# Stimulation_Stage.net
KiCad netlist of a schematic drawn in Altium Designer
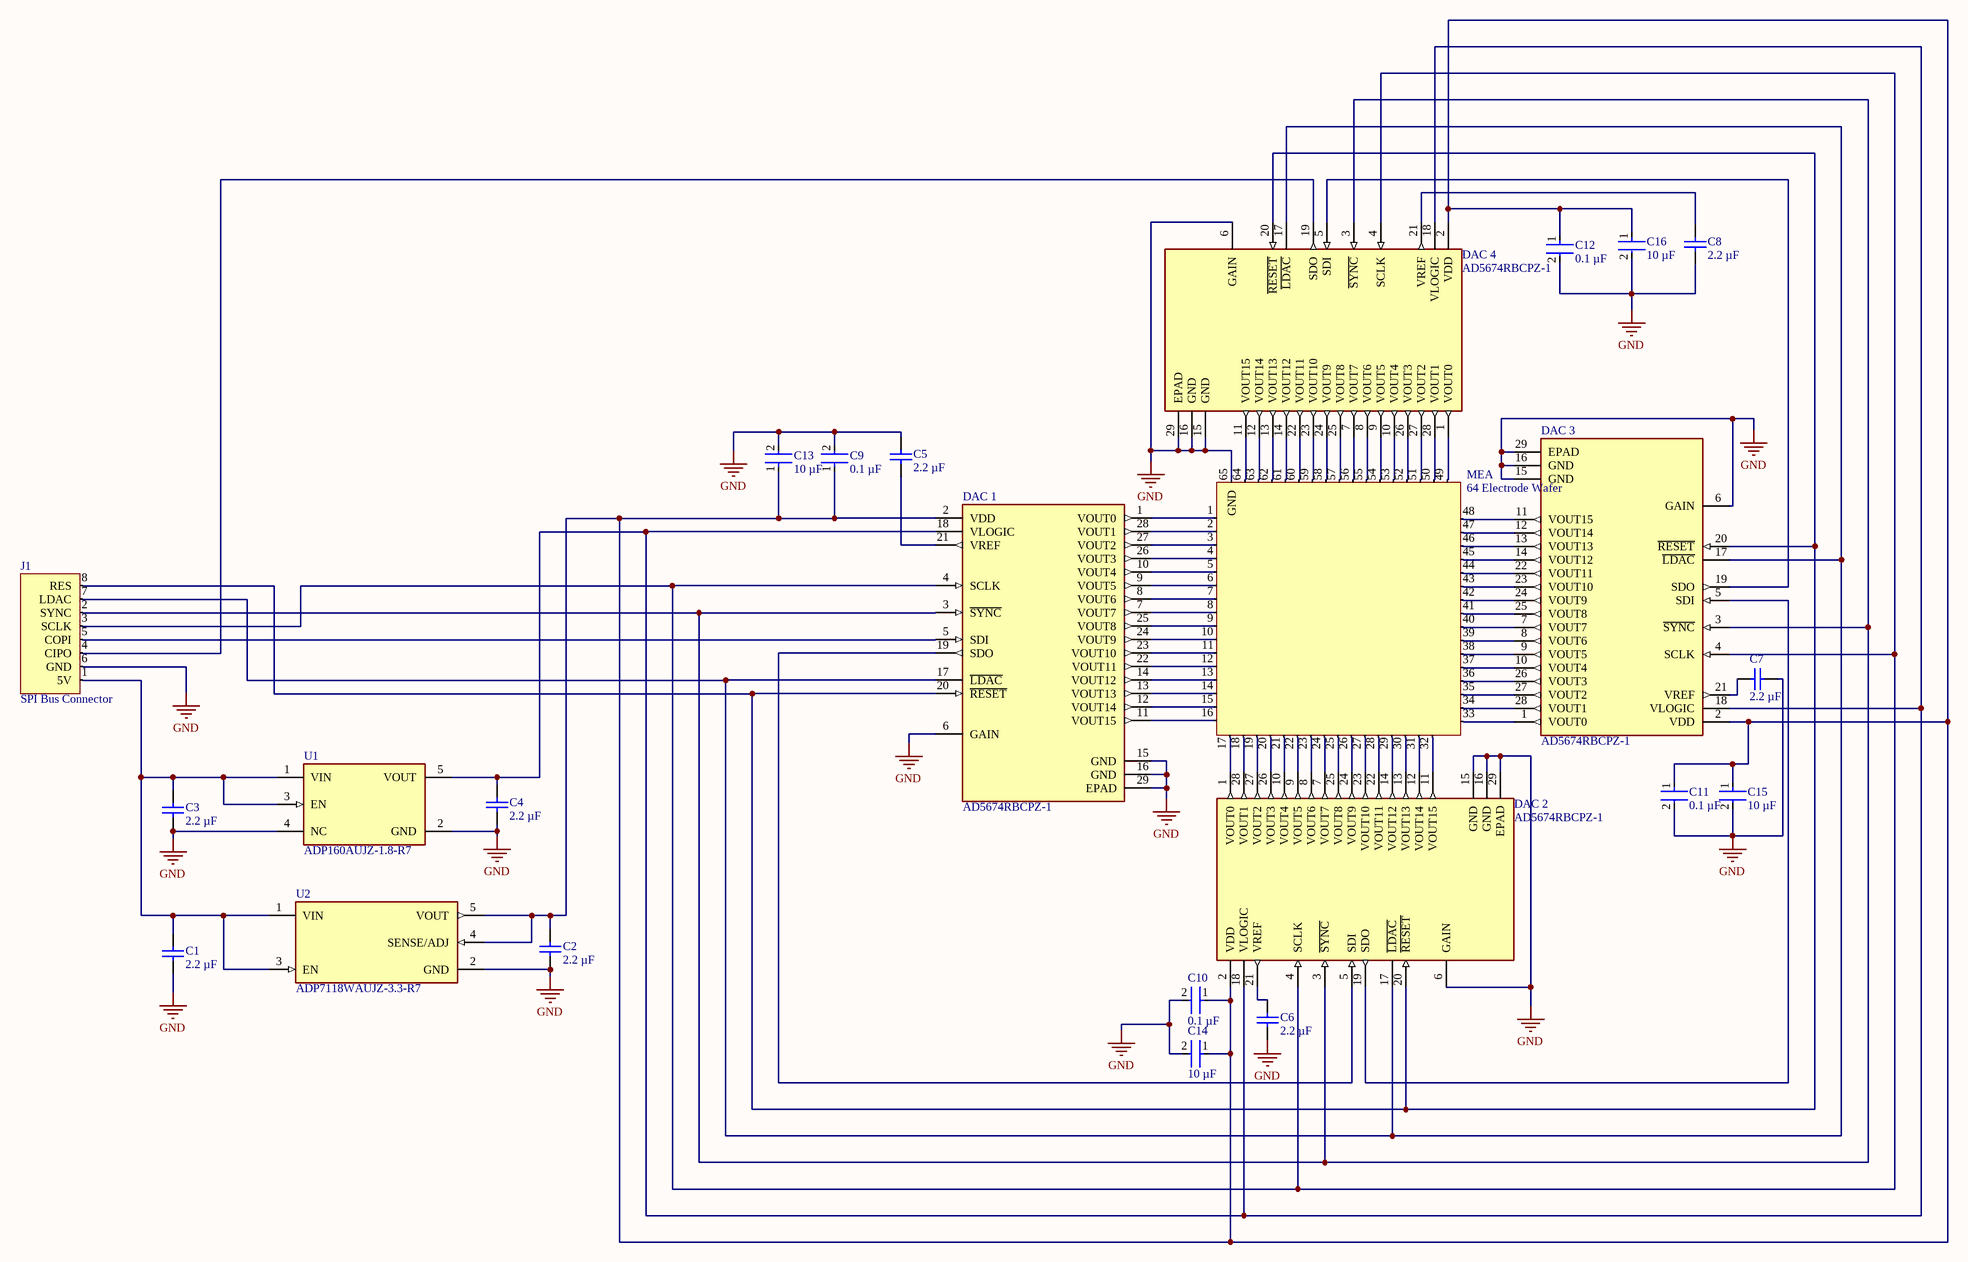
[diagram p0: Stimulation Stage.SchDoc]

(export (version "E")
  (design (tool "Eeschema 10.0.6"))
  (components
    (comp (ref "C1")
      (value "2.2 µF")
      (footprint "CAPC1608X90X30LL10T20")
      (description "Chip Capacitor, 2.2 uF, +/- 10%, 10 V, -55 to 85 degC, 0603 (1608 Metric), RoHS, Tape and Reel")
      (fields (field (name "MANUFACTURER") "Samsung Electro-Mechanics"))
      (libsource (lib "Altium Content Vault") (part "CAP-NP-2"))
    )
    (comp (ref "C2")
      (value "2.2 µF")
      (footprint "CAPC1608X90X30LL10T20")
      (description "Chip Capacitor, 2.2 uF, +/- 10%, 10 V, -55 to 85 degC, 0603 (1608 Metric), RoHS, Tape and Reel")
      (fields (field (name "MANUFACTURER") "Samsung Electro-Mechanics"))
      (libsource (lib "Altium Content Vault") (part "CAP-NP-2"))
    )
    (comp (ref "C3")
      (value "2.2 µF")
      (footprint "CAPC1608X90X30LL10T20")
      (description "Chip Capacitor, 2.2 uF, +/- 10%, 10 V, -55 to 85 degC, 0603 (1608 Metric), RoHS, Tape and Reel")
      (fields (field (name "MANUFACTURER") "Samsung Electro-Mechanics"))
      (libsource (lib "Altium Content Vault") (part "CAP-NP-2"))
    )
    (comp (ref "C4")
      (value "2.2 µF")
      (footprint "CAPC1608X90X30LL10T20")
      (description "Chip Capacitor, 2.2 uF, +/- 10%, 10 V, -55 to 85 degC, 0603 (1608 Metric), RoHS, Tape and Reel")
      (fields (field (name "MANUFACTURER") "Samsung Electro-Mechanics"))
      (libsource (lib "Altium Content Vault") (part "CAP-NP-2"))
    )
    (comp (ref "C5")
      (value "2.2 µF")
      (footprint "CAPC1608X90X30LL10T20")
      (description "Chip Capacitor, 2.2 uF, +/- 10%, 10 V, -55 to 85 degC, 0603 (1608 Metric), RoHS, Tape and Reel")
      (fields (field (name "MANUFACTURER") "Samsung Electro-Mechanics"))
      (libsource (lib "Altium Content Vault") (part "CAP-NP-2"))
    )
    (comp (ref "C6")
      (value "2.2 µF")
      (footprint "CAPC1608X90X30LL10T20")
      (description "Chip Capacitor, 2.2 uF, +/- 10%, 10 V, -55 to 85 degC, 0603 (1608 Metric), RoHS, Tape and Reel")
      (fields (field (name "MANUFACTURER") "Samsung Electro-Mechanics"))
      (libsource (lib "Altium Content Vault") (part "CAP-NP-2"))
    )
    (comp (ref "C7")
      (value "2.2 µF")
      (footprint "CAPC1608X90X30LL10T20")
      (description "Chip Capacitor, 2.2 uF, +/- 10%, 10 V, -55 to 85 degC, 0603 (1608 Metric), RoHS, Tape and Reel")
      (fields (field (name "MANUFACTURER") "Samsung Electro-Mechanics"))
      (libsource (lib "Altium Content Vault") (part "CAP-NP-2"))
    )
    (comp (ref "C8")
      (value "2.2 µF")
      (footprint "CAPC1608X90X30LL10T20")
      (description "Chip Capacitor, 2.2 uF, +/- 10%, 10 V, -55 to 85 degC, 0603 (1608 Metric), RoHS, Tape and Reel")
      (fields (field (name "MANUFACTURER") "Samsung Electro-Mechanics"))
      (libsource (lib "Altium Content Vault") (part "CAP-NP-2"))
    )
    (comp (ref "C9")
      (value "0.1 µF")
      (footprint "FP-CL278-IPC_C")
      (description "Cap Ceramic 100nF 25V X5R ±10% SMD 0402 +85°C Paper T/R")
      (fields (field (name "VOLTAGE") "25V") (field (name "TOLERANCE") "10%"))
      (libsource (lib "Altium Content Vault") (part "b4654b650e69147ec39a6b967a45e02"))
    )
    (comp (ref "C10")
      (value "0.1 µF")
      (footprint "FP-CL278-IPC_C")
      (description "Cap Ceramic 100nF 25V X5R ±10% SMD 0402 +85°C Paper T/R")
      (fields (field (name "VOLTAGE") "25V") (field (name "TOLERANCE") "10%"))
      (libsource (lib "Altium Content Vault") (part "b4654b650e69147ec39a6b967a45e02"))
    )
    (comp (ref "C11")
      (value "0.1 µF")
      (footprint "FP-CL278-IPC_C")
      (description "Cap Ceramic 100nF 25V X5R ±10% SMD 0402 +85°C Paper T/R")
      (fields (field (name "VOLTAGE") "25V") (field (name "TOLERANCE") "10%"))
      (libsource (lib "Altium Content Vault") (part "b4654b650e69147ec39a6b967a45e02"))
    )
    (comp (ref "C12")
      (value "0.1 µF")
      (footprint "FP-CL278-IPC_C")
      (description "Cap Ceramic 100nF 25V X5R ±10% SMD 0402 +85°C Paper T/R")
      (fields (field (name "VOLTAGE") "25V") (field (name "TOLERANCE") "10%"))
      (libsource (lib "Altium Content Vault") (part "b4654b650e69147ec39a6b967a45e02"))
    )
    (comp (ref "C13")
      (value "10 µF")
      (footprint "FP-CL10-IPC_C")
      (description "Cap Ceramic 10uF 6.3V X5R ±20% Pad SMD 0603 +85°C T/R")
      (fields (field (name "VOLTAGE") "6.3V") (field (name "TOLERANCE") "20%"))
      (libsource (lib "Altium Content Vault") (part "b4654b650e69147ec39a6b967a45e02"))
    )
    (comp (ref "C14")
      (value "10 µF")
      (footprint "FP-CL10-IPC_C")
      (description "Cap Ceramic 10uF 6.3V X5R ±20% Pad SMD 0603 +85°C T/R")
      (fields (field (name "VOLTAGE") "6.3V") (field (name "TOLERANCE") "20%"))
      (libsource (lib "Altium Content Vault") (part "b4654b650e69147ec39a6b967a45e02"))
    )
    (comp (ref "C15")
      (value "10 µF")
      (footprint "FP-CL10-IPC_C")
      (description "Cap Ceramic 10uF 6.3V X5R ±20% Pad SMD 0603 +85°C T/R")
      (fields (field (name "VOLTAGE") "6.3V") (field (name "TOLERANCE") "20%"))
      (libsource (lib "Altium Content Vault") (part "b4654b650e69147ec39a6b967a45e02"))
    )
    (comp (ref "C16")
      (value "10 µF")
      (footprint "FP-CL10-IPC_C")
      (description "Cap Ceramic 10uF 6.3V X5R ±20% Pad SMD 0603 +85°C T/R")
      (fields (field (name "VOLTAGE") "6.3V") (field (name "TOLERANCE") "20%"))
      (libsource (lib "Altium Content Vault") (part "b4654b650e69147ec39a6b967a45e02"))
    )
    (comp (ref "DAC 1")
      (value "AD5674RBCPZ-1")
      (footprint "FP-CP-28-9-IPC_C")
      (description "16-CH12-BITNANODAC+WITH2PPM/CREF")
      (libsource (lib "") (part "8444db3836bae7896dad1ad18e8f2a5_2"))
    )
    (comp (ref "DAC 2")
      (value "AD5674RBCPZ-1")
      (footprint "FP-CP-28-9-IPC_C")
      (description "16-CH12-BITNANODAC+WITH2PPM/CREF")
      (libsource (lib "") (part "8444db3836bae7896dad1ad18e8f2a5_1"))
    )
    (comp (ref "DAC 3")
      (value "AD5674RBCPZ-1")
      (footprint "FP-CP-28-9-IPC_C")
      (description "16-CH12-BITNANODAC+WITH2PPM/CREF")
      (libsource (lib "Altium Content Vault") (part "8444db3836bae7896dad1ad18e8f2a5"))
    )
    (comp (ref "DAC 4")
      (value "AD5674RBCPZ-1")
      (footprint "FP-CP-28-9-IPC_C")
      (description "16-CH12-BITNANODAC+WITH2PPM/CREF")
      (libsource (lib "") (part "8444db3836bae7896dad1ad18e8f2a5_3"))
    )
    (comp (ref "J1")
      (value "SPI Bus Connector")
      (footprint "SPI Bus Connector")
      (description "8 pin connector for SPI interface and power from m")
      (libsource (lib "Celestial Library Database") (part "SPI Bus Connector"))
    )
    (comp (ref "MEA")
      (value "64 Electrode Wafer")
      (footprint "64 Electrode Wafer Footprint")
      (description "64 channel transparent Microelectrode Array")
      (libsource (lib "Celestial Library Database") (part "64 Electrode Wafer"))
    )
    (comp (ref "U1")
      (value "ADP160AUJZ-1.8-R7")
      (footprint "FP-UJ-5-IPC_C")
      (description "IC REG LINEAR 1.8V 150MA TSOT5")
      (libsource (lib "Altium Content Vault") (part "49efecb8457b62bbb278fcbf558b656"))
    )
    (comp (ref "U2")
      (value "ADP7118WAUJZ-3.3-R7")
      (footprint "FP-UJ-5-IPC_C")
      (description "IC REG LINEAR 3.3V 200MA TSOT5")
      (libsource (lib "Altium Content Vault") (part "4a7971eea0f250dff842508c33254cb"))
    )
  )
  (nets
    (net (code "1") (name "GND") (class "Default")
      (node (ref "C1") (pin "1") (pinfunction "1_1") (pintype "passive"))
      (node (ref "C10") (pin "2") (pinfunction "2_2") (pintype "passive"))
      (node (ref "C11") (pin "2") (pinfunction "2_2") (pintype "passive"))
      (node (ref "C12") (pin "2") (pinfunction "2_2") (pintype "passive"))
      (node (ref "C13") (pin "2") (pinfunction "2_2") (pintype "passive"))
      (node (ref "C14") (pin "2") (pinfunction "2_2") (pintype "passive"))
      (node (ref "C15") (pin "2") (pinfunction "2_2") (pintype "passive"))
      (node (ref "C16") (pin "2") (pinfunction "2_2") (pintype "passive"))
      (node (ref "C2") (pin "1") (pinfunction "1_1") (pintype "passive"))
      (node (ref "C3") (pin "1") (pinfunction "1_1") (pintype "passive"))
      (node (ref "C4") (pin "1") (pinfunction "1_1") (pintype "passive"))
      (node (ref "C5") (pin "2") (pinfunction "2_2") (pintype "passive"))
      (node (ref "C6") (pin "1") (pinfunction "1_1") (pintype "passive"))
      (node (ref "C7") (pin "1") (pinfunction "1_1") (pintype "passive"))
      (node (ref "C8") (pin "1") (pinfunction "1_1") (pintype "passive"))
      (node (ref "C9") (pin "2") (pinfunction "2_2") (pintype "passive"))
      (node (ref "DAC 1") (pin "15") (pinfunction "GND_15") (pintype "power_in"))
      (node (ref "DAC 1") (pin "16") (pinfunction "GND_16") (pintype "power_in"))
      (node (ref "DAC 1") (pin "29") (pinfunction "EPAD_29") (pintype "power_in"))
      (node (ref "DAC 1") (pin "6") (pinfunction "GAIN_6") (pintype "passive"))
      (node (ref "DAC 2") (pin "15") (pinfunction "GND_15") (pintype "power_in"))
      (node (ref "DAC 2") (pin "16") (pinfunction "GND_16") (pintype "power_in"))
      (node (ref "DAC 2") (pin "29") (pinfunction "EPAD_29") (pintype "power_in"))
      (node (ref "DAC 2") (pin "6") (pinfunction "GAIN_6") (pintype "passive"))
      (node (ref "DAC 3") (pin "15") (pinfunction "GND_15") (pintype "power_in"))
      (node (ref "DAC 3") (pin "16") (pinfunction "GND_16") (pintype "power_in"))
      (node (ref "DAC 3") (pin "29") (pinfunction "EPAD_29") (pintype "power_in"))
      (node (ref "DAC 3") (pin "6") (pinfunction "GAIN_6") (pintype "passive"))
      (node (ref "DAC 4") (pin "15") (pinfunction "GND_15") (pintype "power_in"))
      (node (ref "DAC 4") (pin "16") (pinfunction "GND_16") (pintype "power_in"))
      (node (ref "DAC 4") (pin "29") (pinfunction "EPAD_29") (pintype "power_in"))
      (node (ref "DAC 4") (pin "6") (pinfunction "GAIN_6") (pintype "passive"))
      (node (ref "J1") (pin "6") (pinfunction "GND_6") (pintype "power_in"))
      (node (ref "MEA") (pin "65") (pinfunction "GND_65") (pintype "input"))
      (node (ref "U1") (pin "2") (pinfunction "GND_2") (pintype "power_in"))
      (node (ref "U1") (pin "4") (pinfunction "NC_4") (pintype "passive"))
      (node (ref "U2") (pin "2") (pinfunction "GND_2") (pintype "power_in"))
    )
    (net (code "2") (name "Net-(DAC 1-SCLK)") (class "Default")
      (node (ref "DAC 1") (pin "4") (pinfunction "SCLK_4") (pintype "input"))
      (node (ref "DAC 2") (pin "4") (pinfunction "SCLK_4") (pintype "input"))
      (node (ref "DAC 3") (pin "4") (pinfunction "SCLK_4") (pintype "input"))
      (node (ref "DAC 4") (pin "4") (pinfunction "SCLK_4") (pintype "input"))
      (node (ref "J1") (pin "3") (pinfunction "SCLK_3") (pintype "output"))
    )
    (net (code "3") (name "Net-(DAC 1-SDI)") (class "Default")
      (node (ref "DAC 1") (pin "5") (pinfunction "SDI_5") (pintype "input"))
      (node (ref "J1") (pin "5") (pinfunction "COPI_5") (pintype "output"))
    )
    (net (code "4") (name "Net-(DAC 1-SDO)") (class "Default")
      (node (ref "DAC 1") (pin "19") (pinfunction "SDO_19") (pintype "output"))
      (node (ref "DAC 2") (pin "5") (pinfunction "SDI_5") (pintype "input"))
    )
    (net (code "5") (name "Net-(DAC 1-VDD)") (class "Default")
      (node (ref "C10") (pin "1") (pinfunction "1_1") (pintype "passive"))
      (node (ref "C11") (pin "1") (pinfunction "1_1") (pintype "passive"))
      (node (ref "C12") (pin "1") (pinfunction "1_1") (pintype "passive"))
      (node (ref "C13") (pin "1") (pinfunction "1_1") (pintype "passive"))
      (node (ref "C14") (pin "1") (pinfunction "1_1") (pintype "passive"))
      (node (ref "C15") (pin "1") (pinfunction "1_1") (pintype "passive"))
      (node (ref "C16") (pin "1") (pinfunction "1_1") (pintype "passive"))
      (node (ref "C2") (pin "2") (pinfunction "2_2") (pintype "passive"))
      (node (ref "C9") (pin "1") (pinfunction "1_1") (pintype "passive"))
      (node (ref "DAC 1") (pin "2") (pinfunction "VDD_2") (pintype "power_in"))
      (node (ref "DAC 2") (pin "2") (pinfunction "VDD_2") (pintype "power_in"))
      (node (ref "DAC 3") (pin "2") (pinfunction "VDD_2") (pintype "power_in"))
      (node (ref "DAC 4") (pin "2") (pinfunction "VDD_2") (pintype "power_in"))
      (node (ref "U2") (pin "4") (pinfunction "SENSE/ADJ_4") (pintype "input"))
      (node (ref "U2") (pin "5") (pinfunction "VOUT_5") (pintype "output"))
    )
    (net (code "6") (name "Net-(DAC 1-VLOGIC)") (class "Default")
      (node (ref "C4") (pin "2") (pinfunction "2_2") (pintype "passive"))
      (node (ref "DAC 1") (pin "18") (pinfunction "VLOGIC_18") (pintype "power_in"))
      (node (ref "DAC 2") (pin "18") (pinfunction "VLOGIC_18") (pintype "power_in"))
      (node (ref "DAC 3") (pin "18") (pinfunction "VLOGIC_18") (pintype "power_in"))
      (node (ref "DAC 4") (pin "18") (pinfunction "VLOGIC_18") (pintype "power_in"))
      (node (ref "U1") (pin "5") (pinfunction "VOUT_5") (pintype "power_in"))
    )
    (net (code "7") (name "Net-(DAC 1-VOUT0)") (class "Default")
      (node (ref "DAC 1") (pin "1") (pinfunction "VOUT0_1") (pintype "output"))
      (node (ref "MEA") (pin "1") (pintype "input"))
    )
    (net (code "8") (name "Net-(DAC 1-VOUT1)") (class "Default")
      (node (ref "DAC 1") (pin "28") (pinfunction "VOUT1_28") (pintype "output"))
      (node (ref "MEA") (pin "2") (pintype "input"))
    )
    (net (code "9") (name "Net-(DAC 1-VOUT2)") (class "Default")
      (node (ref "DAC 1") (pin "27") (pinfunction "VOUT2_27") (pintype "output"))
      (node (ref "MEA") (pin "3") (pintype "input"))
    )
    (net (code "10") (name "Net-(DAC 1-VOUT3)") (class "Default")
      (node (ref "DAC 1") (pin "26") (pinfunction "VOUT3_26") (pintype "output"))
      (node (ref "MEA") (pin "4") (pintype "input"))
    )
    (net (code "11") (name "Net-(DAC 1-VOUT4)") (class "Default")
      (node (ref "DAC 1") (pin "10") (pinfunction "VOUT4_10") (pintype "output"))
      (node (ref "MEA") (pin "5") (pintype "input"))
    )
    (net (code "12") (name "Net-(DAC 1-VOUT5)") (class "Default")
      (node (ref "DAC 1") (pin "9") (pinfunction "VOUT5_9") (pintype "output"))
      (node (ref "MEA") (pin "6") (pintype "input"))
    )
    (net (code "13") (name "Net-(DAC 1-VOUT6)") (class "Default")
      (node (ref "DAC 1") (pin "8") (pinfunction "VOUT6_8") (pintype "output"))
      (node (ref "MEA") (pin "7") (pintype "input"))
    )
    (net (code "14") (name "Net-(DAC 1-VOUT7)") (class "Default")
      (node (ref "DAC 1") (pin "7") (pinfunction "VOUT7_7") (pintype "output"))
      (node (ref "MEA") (pin "8") (pintype "input"))
    )
    (net (code "15") (name "Net-(DAC 1-VOUT8)") (class "Default")
      (node (ref "DAC 1") (pin "25") (pinfunction "VOUT8_25") (pintype "output"))
      (node (ref "MEA") (pin "9") (pintype "input"))
    )
    (net (code "16") (name "Net-(DAC 1-VOUT9)") (class "Default")
      (node (ref "DAC 1") (pin "24") (pinfunction "VOUT9_24") (pintype "output"))
      (node (ref "MEA") (pin "10") (pintype "input"))
    )
    (net (code "17") (name "Net-(DAC 1-VOUT10)") (class "Default")
      (node (ref "DAC 1") (pin "23") (pinfunction "VOUT10_23") (pintype "output"))
      (node (ref "MEA") (pin "11") (pintype "input"))
    )
    (net (code "18") (name "Net-(DAC 1-VOUT11)") (class "Default")
      (node (ref "DAC 1") (pin "22") (pinfunction "VOUT11_22") (pintype "output"))
      (node (ref "MEA") (pin "12") (pintype "input"))
    )
    (net (code "19") (name "Net-(DAC 1-VOUT12)") (class "Default")
      (node (ref "DAC 1") (pin "14") (pinfunction "VOUT12_14") (pintype "output"))
      (node (ref "MEA") (pin "13") (pintype "input"))
    )
    (net (code "20") (name "Net-(DAC 1-VOUT13)") (class "Default")
      (node (ref "DAC 1") (pin "13") (pinfunction "VOUT13_13") (pintype "output"))
      (node (ref "MEA") (pin "14") (pintype "input"))
    )
    (net (code "21") (name "Net-(DAC 1-VOUT14)") (class "Default")
      (node (ref "DAC 1") (pin "12") (pinfunction "VOUT14_12") (pintype "output"))
      (node (ref "MEA") (pin "15") (pintype "input"))
    )
    (net (code "22") (name "Net-(DAC 1-VOUT15)") (class "Default")
      (node (ref "DAC 1") (pin "11") (pinfunction "VOUT15_11") (pintype "output"))
      (node (ref "MEA") (pin "16") (pintype "input"))
    )
    (net (code "23") (name "Net-(DAC 1-VREF)") (class "Default")
      (node (ref "C5") (pin "1") (pinfunction "1_1") (pintype "passive"))
      (node (ref "DAC 1") (pin "21") (pinfunction "VREF_21") (pintype "output"))
    )
    (net (code "24") (name "Net-(DAC 1-~{LDAC})") (class "Default")
      (node (ref "DAC 1") (pin "17") (pinfunction "~{LDAC}_17") (pintype "passive"))
      (node (ref "DAC 2") (pin "17") (pinfunction "~{LDAC}_17") (pintype "passive"))
      (node (ref "DAC 3") (pin "17") (pinfunction "~{LDAC}_17") (pintype "passive"))
      (node (ref "DAC 4") (pin "17") (pinfunction "~{LDAC}_17") (pintype "passive"))
      (node (ref "J1") (pin "7") (pinfunction "LDAC_7") (pintype "output"))
    )
    (net (code "25") (name "Net-(DAC 1-~{RESET})") (class "Default")
      (node (ref "DAC 1") (pin "20") (pinfunction "~{RESET}_20") (pintype "input"))
      (node (ref "DAC 2") (pin "20") (pinfunction "~{RESET}_20") (pintype "input"))
      (node (ref "DAC 3") (pin "20") (pinfunction "~{RESET}_20") (pintype "input"))
      (node (ref "DAC 4") (pin "20") (pinfunction "~{RESET}_20") (pintype "input"))
      (node (ref "J1") (pin "8") (pinfunction "RES_8") (pintype "output"))
    )
    (net (code "26") (name "Net-(DAC 1-~{SYNC})") (class "Default")
      (node (ref "DAC 1") (pin "3") (pinfunction "~{SYNC}_3") (pintype "input"))
      (node (ref "DAC 2") (pin "3") (pinfunction "~{SYNC}_3") (pintype "input"))
      (node (ref "DAC 3") (pin "3") (pinfunction "~{SYNC}_3") (pintype "input"))
      (node (ref "DAC 4") (pin "3") (pinfunction "~{SYNC}_3") (pintype "input"))
      (node (ref "J1") (pin "2") (pinfunction "SYNC_2") (pintype "output"))
    )
    (net (code "27") (name "Net-(DAC 2-SDO)") (class "Default")
      (node (ref "DAC 2") (pin "19") (pinfunction "SDO_19") (pintype "output"))
      (node (ref "DAC 3") (pin "5") (pinfunction "SDI_5") (pintype "input"))
    )
    (net (code "28") (name "Net-(DAC 2-VOUT0)") (class "Default")
      (node (ref "DAC 2") (pin "1") (pinfunction "VOUT0_1") (pintype "output"))
      (node (ref "MEA") (pin "17") (pintype "input"))
    )
    (net (code "29") (name "Net-(DAC 2-VOUT1)") (class "Default")
      (node (ref "DAC 2") (pin "28") (pinfunction "VOUT1_28") (pintype "output"))
      (node (ref "MEA") (pin "18") (pintype "input"))
    )
    (net (code "30") (name "Net-(DAC 2-VOUT2)") (class "Default")
      (node (ref "DAC 2") (pin "27") (pinfunction "VOUT2_27") (pintype "output"))
      (node (ref "MEA") (pin "19") (pintype "input"))
    )
    (net (code "31") (name "Net-(DAC 2-VOUT3)") (class "Default")
      (node (ref "DAC 2") (pin "26") (pinfunction "VOUT3_26") (pintype "output"))
      (node (ref "MEA") (pin "20") (pintype "input"))
    )
    (net (code "32") (name "Net-(DAC 2-VOUT4)") (class "Default")
      (node (ref "DAC 2") (pin "10") (pinfunction "VOUT4_10") (pintype "output"))
      (node (ref "MEA") (pin "21") (pintype "input"))
    )
    (net (code "33") (name "Net-(DAC 2-VOUT5)") (class "Default")
      (node (ref "DAC 2") (pin "9") (pinfunction "VOUT5_9") (pintype "output"))
      (node (ref "MEA") (pin "22") (pintype "input"))
    )
    (net (code "34") (name "Net-(DAC 2-VOUT6)") (class "Default")
      (node (ref "DAC 2") (pin "8") (pinfunction "VOUT6_8") (pintype "output"))
      (node (ref "MEA") (pin "23") (pintype "input"))
    )
    (net (code "35") (name "Net-(DAC 2-VOUT7)") (class "Default")
      (node (ref "DAC 2") (pin "7") (pinfunction "VOUT7_7") (pintype "output"))
      (node (ref "MEA") (pin "24") (pintype "input"))
    )
    (net (code "36") (name "Net-(DAC 2-VOUT8)") (class "Default")
      (node (ref "DAC 2") (pin "25") (pinfunction "VOUT8_25") (pintype "output"))
      (node (ref "MEA") (pin "25") (pintype "input"))
    )
    (net (code "37") (name "Net-(DAC 2-VOUT9)") (class "Default")
      (node (ref "DAC 2") (pin "24") (pinfunction "VOUT9_24") (pintype "output"))
      (node (ref "MEA") (pin "26") (pintype "input"))
    )
    (net (code "38") (name "Net-(DAC 2-VOUT10)") (class "Default")
      (node (ref "DAC 2") (pin "23") (pinfunction "VOUT10_23") (pintype "output"))
      (node (ref "MEA") (pin "27") (pintype "input"))
    )
    (net (code "39") (name "Net-(DAC 2-VOUT11)") (class "Default")
      (node (ref "DAC 2") (pin "22") (pinfunction "VOUT11_22") (pintype "output"))
      (node (ref "MEA") (pin "28") (pintype "input"))
    )
    (net (code "40") (name "Net-(DAC 2-VOUT12)") (class "Default")
      (node (ref "DAC 2") (pin "14") (pinfunction "VOUT12_14") (pintype "output"))
      (node (ref "MEA") (pin "29") (pintype "input"))
    )
    (net (code "41") (name "Net-(DAC 2-VOUT13)") (class "Default")
      (node (ref "DAC 2") (pin "13") (pinfunction "VOUT13_13") (pintype "output"))
      (node (ref "MEA") (pin "30") (pintype "input"))
    )
    (net (code "42") (name "Net-(DAC 2-VOUT14)") (class "Default")
      (node (ref "DAC 2") (pin "12") (pinfunction "VOUT14_12") (pintype "output"))
      (node (ref "MEA") (pin "31") (pintype "input"))
    )
    (net (code "43") (name "Net-(DAC 2-VOUT15)") (class "Default")
      (node (ref "DAC 2") (pin "11") (pinfunction "VOUT15_11") (pintype "output"))
      (node (ref "MEA") (pin "32") (pintype "input"))
    )
    (net (code "44") (name "Net-(DAC 2-VREF)") (class "Default")
      (node (ref "C6") (pin "2") (pinfunction "2_2") (pintype "passive"))
      (node (ref "DAC 2") (pin "21") (pinfunction "VREF_21") (pintype "output"))
    )
    (net (code "45") (name "Net-(DAC 3-SDO)") (class "Default")
      (node (ref "DAC 3") (pin "19") (pinfunction "SDO_19") (pintype "output"))
      (node (ref "DAC 4") (pin "5") (pinfunction "SDI_5") (pintype "input"))
    )
    (net (code "46") (name "Net-(DAC 3-VOUT0)") (class "Default")
      (node (ref "DAC 3") (pin "1") (pinfunction "VOUT0_1") (pintype "output"))
      (node (ref "MEA") (pin "33") (pintype "input"))
    )
    (net (code "47") (name "Net-(DAC 3-VOUT1)") (class "Default")
      (node (ref "DAC 3") (pin "28") (pinfunction "VOUT1_28") (pintype "output"))
      (node (ref "MEA") (pin "34") (pintype "input"))
    )
    (net (code "48") (name "Net-(DAC 3-VOUT2)") (class "Default")
      (node (ref "DAC 3") (pin "27") (pinfunction "VOUT2_27") (pintype "output"))
      (node (ref "MEA") (pin "35") (pintype "input"))
    )
    (net (code "49") (name "Net-(DAC 3-VOUT3)") (class "Default")
      (node (ref "DAC 3") (pin "26") (pinfunction "VOUT3_26") (pintype "output"))
      (node (ref "MEA") (pin "36") (pintype "input"))
    )
    (net (code "50") (name "Net-(DAC 3-VOUT4)") (class "Default")
      (node (ref "DAC 3") (pin "10") (pinfunction "VOUT4_10") (pintype "output"))
      (node (ref "MEA") (pin "37") (pintype "input"))
    )
    (net (code "51") (name "Net-(DAC 3-VOUT5)") (class "Default")
      (node (ref "DAC 3") (pin "9") (pinfunction "VOUT5_9") (pintype "output"))
      (node (ref "MEA") (pin "38") (pintype "input"))
    )
    (net (code "52") (name "Net-(DAC 3-VOUT6)") (class "Default")
      (node (ref "DAC 3") (pin "8") (pinfunction "VOUT6_8") (pintype "output"))
      (node (ref "MEA") (pin "39") (pintype "input"))
    )
    (net (code "53") (name "Net-(DAC 3-VOUT7)") (class "Default")
      (node (ref "DAC 3") (pin "7") (pinfunction "VOUT7_7") (pintype "output"))
      (node (ref "MEA") (pin "40") (pintype "input"))
    )
    (net (code "54") (name "Net-(DAC 3-VOUT8)") (class "Default")
      (node (ref "DAC 3") (pin "25") (pinfunction "VOUT8_25") (pintype "output"))
      (node (ref "MEA") (pin "41") (pintype "input"))
    )
    (net (code "55") (name "Net-(DAC 3-VOUT9)") (class "Default")
      (node (ref "DAC 3") (pin "24") (pinfunction "VOUT9_24") (pintype "output"))
      (node (ref "MEA") (pin "42") (pintype "input"))
    )
    (net (code "56") (name "Net-(DAC 3-VOUT10)") (class "Default")
      (node (ref "DAC 3") (pin "23") (pinfunction "VOUT10_23") (pintype "output"))
      (node (ref "MEA") (pin "43") (pintype "input"))
    )
    (net (code "57") (name "Net-(DAC 3-VOUT11)") (class "Default")
      (node (ref "DAC 3") (pin "22") (pinfunction "VOUT11_22") (pintype "output"))
      (node (ref "MEA") (pin "44") (pintype "input"))
    )
    (net (code "58") (name "Net-(DAC 3-VOUT12)") (class "Default")
      (node (ref "DAC 3") (pin "14") (pinfunction "VOUT12_14") (pintype "output"))
      (node (ref "MEA") (pin "45") (pintype "input"))
    )
    (net (code "59") (name "Net-(DAC 3-VOUT13)") (class "Default")
      (node (ref "DAC 3") (pin "13") (pinfunction "VOUT13_13") (pintype "output"))
      (node (ref "MEA") (pin "46") (pintype "input"))
    )
    (net (code "60") (name "Net-(DAC 3-VOUT14)") (class "Default")
      (node (ref "DAC 3") (pin "12") (pinfunction "VOUT14_12") (pintype "output"))
      (node (ref "MEA") (pin "47") (pintype "input"))
    )
    (net (code "61") (name "Net-(DAC 3-VOUT15)") (class "Default")
      (node (ref "DAC 3") (pin "11") (pinfunction "VOUT15_11") (pintype "output"))
      (node (ref "MEA") (pin "48") (pintype "input"))
    )
    (net (code "62") (name "Net-(DAC 3-VREF)") (class "Default")
      (node (ref "C7") (pin "2") (pinfunction "2_2") (pintype "passive"))
      (node (ref "DAC 3") (pin "21") (pinfunction "VREF_21") (pintype "output"))
    )
    (net (code "63") (name "Net-(DAC 4-SDO)") (class "Default")
      (node (ref "DAC 4") (pin "19") (pinfunction "SDO_19") (pintype "output"))
      (node (ref "J1") (pin "4") (pinfunction "CIPO_4") (pintype "input"))
    )
    (net (code "64") (name "Net-(DAC 4-VOUT0)") (class "Default")
      (node (ref "DAC 4") (pin "1") (pinfunction "VOUT0_1") (pintype "output"))
      (node (ref "MEA") (pin "49") (pintype "input"))
    )
    (net (code "65") (name "Net-(DAC 4-VOUT1)") (class "Default")
      (node (ref "DAC 4") (pin "28") (pinfunction "VOUT1_28") (pintype "output"))
      (node (ref "MEA") (pin "50") (pintype "input"))
    )
    (net (code "66") (name "Net-(DAC 4-VOUT2)") (class "Default")
      (node (ref "DAC 4") (pin "27") (pinfunction "VOUT2_27") (pintype "output"))
      (node (ref "MEA") (pin "51") (pintype "input"))
    )
    (net (code "67") (name "Net-(DAC 4-VOUT3)") (class "Default")
      (node (ref "DAC 4") (pin "26") (pinfunction "VOUT3_26") (pintype "output"))
      (node (ref "MEA") (pin "52") (pintype "input"))
    )
    (net (code "68") (name "Net-(DAC 4-VOUT4)") (class "Default")
      (node (ref "DAC 4") (pin "10") (pinfunction "VOUT4_10") (pintype "output"))
      (node (ref "MEA") (pin "53") (pintype "input"))
    )
    (net (code "69") (name "Net-(DAC 4-VOUT5)") (class "Default")
      (node (ref "DAC 4") (pin "9") (pinfunction "VOUT5_9") (pintype "output"))
      (node (ref "MEA") (pin "54") (pintype "input"))
    )
    (net (code "70") (name "Net-(DAC 4-VOUT6)") (class "Default")
      (node (ref "DAC 4") (pin "8") (pinfunction "VOUT6_8") (pintype "output"))
      (node (ref "MEA") (pin "55") (pintype "input"))
    )
    (net (code "71") (name "Net-(DAC 4-VOUT7)") (class "Default")
      (node (ref "DAC 4") (pin "7") (pinfunction "VOUT7_7") (pintype "output"))
      (node (ref "MEA") (pin "56") (pintype "input"))
    )
    (net (code "72") (name "Net-(DAC 4-VOUT8)") (class "Default")
      (node (ref "DAC 4") (pin "25") (pinfunction "VOUT8_25") (pintype "output"))
      (node (ref "MEA") (pin "57") (pintype "input"))
    )
    (net (code "73") (name "Net-(DAC 4-VOUT9)") (class "Default")
      (node (ref "DAC 4") (pin "24") (pinfunction "VOUT9_24") (pintype "output"))
      (node (ref "MEA") (pin "58") (pintype "input"))
    )
    (net (code "74") (name "Net-(DAC 4-VOUT10)") (class "Default")
      (node (ref "DAC 4") (pin "23") (pinfunction "VOUT10_23") (pintype "output"))
      (node (ref "MEA") (pin "59") (pintype "input"))
    )
    (net (code "75") (name "Net-(DAC 4-VOUT11)") (class "Default")
      (node (ref "DAC 4") (pin "22") (pinfunction "VOUT11_22") (pintype "output"))
      (node (ref "MEA") (pin "60") (pintype "input"))
    )
    (net (code "76") (name "Net-(DAC 4-VOUT12)") (class "Default")
      (node (ref "DAC 4") (pin "14") (pinfunction "VOUT12_14") (pintype "output"))
      (node (ref "MEA") (pin "61") (pintype "input"))
    )
    (net (code "77") (name "Net-(DAC 4-VOUT13)") (class "Default")
      (node (ref "DAC 4") (pin "13") (pinfunction "VOUT13_13") (pintype "output"))
      (node (ref "MEA") (pin "62") (pintype "input"))
    )
    (net (code "78") (name "Net-(DAC 4-VOUT14)") (class "Default")
      (node (ref "DAC 4") (pin "12") (pinfunction "VOUT14_12") (pintype "output"))
      (node (ref "MEA") (pin "63") (pintype "input"))
    )
    (net (code "79") (name "Net-(DAC 4-VOUT15)") (class "Default")
      (node (ref "DAC 4") (pin "11") (pinfunction "VOUT15_11") (pintype "output"))
      (node (ref "MEA") (pin "64") (pintype "input"))
    )
    (net (code "80") (name "Net-(DAC 4-VREF)") (class "Default")
      (node (ref "C8") (pin "2") (pinfunction "2_2") (pintype "passive"))
      (node (ref "DAC 4") (pin "21") (pinfunction "VREF_21") (pintype "output"))
    )
    (net (code "81") (name "Net-(J1-5V)") (class "Default")
      (node (ref "C1") (pin "2") (pinfunction "2_2") (pintype "passive"))
      (node (ref "C3") (pin "2") (pinfunction "2_2") (pintype "passive"))
      (node (ref "J1") (pin "1") (pinfunction "5V_1") (pintype "power_in"))
      (node (ref "U1") (pin "1") (pinfunction "VIN_1") (pintype "power_in"))
      (node (ref "U1") (pin "3") (pinfunction "EN_3") (pintype "input"))
      (node (ref "U2") (pin "1") (pinfunction "VIN_1") (pintype "power_in"))
      (node (ref "U2") (pin "3") (pinfunction "EN_3") (pintype "input"))
    )
  )
)
